# zasilanie.net
KiCad netlist of a schematic drawn in EAGLE
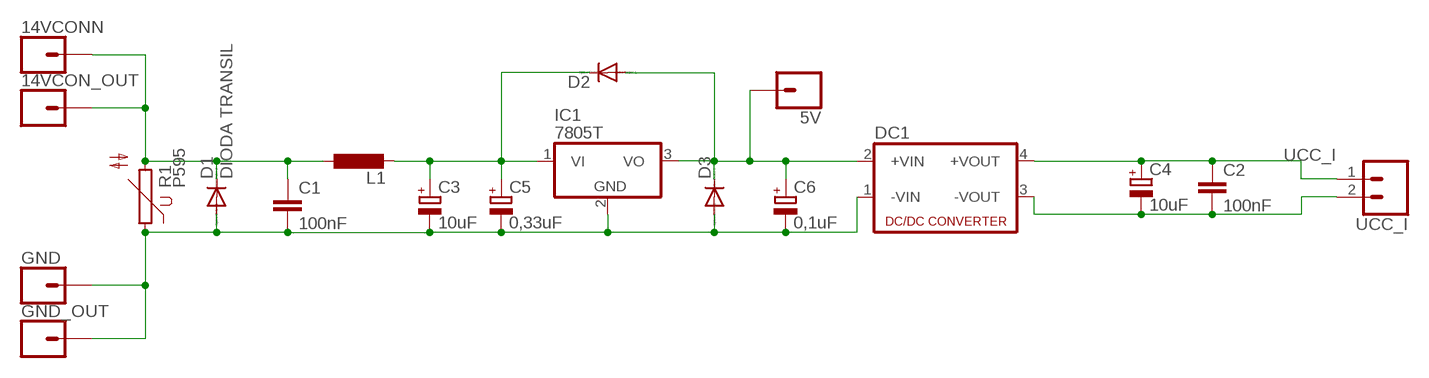
[diagram p0: schematic, sheet 1]

(export (version "E")
  (design (tool "Eeschema 10.0.6"))
  (components
    (comp (ref "5V")
      (value "CONN_01PTH_LONGPAD")
      (footprint "eagle-import:1X01_LONGPAD")
      (libsource (lib "eagle-import") (part "CONN_01PTH_LONGPAD"))
    )
    (comp (ref "14VCONN")
      (value "CONN_01PTH_LONGPAD")
      (footprint "eagle-import:1X01_LONGPAD")
      (libsource (lib "eagle-import") (part "CONN_01PTH_LONGPAD"))
    )
    (comp (ref "14VCON_OUT")
      (value "CONN_01PTH_LONGPAD")
      (footprint "eagle-import:1X01_LONGPAD")
      (libsource (lib "eagle-import") (part "CONN_01PTH_LONGPAD"))
    )
    (comp (ref "C1")
      (value "100nF")
      (footprint "eagle-import:C025-024X044")
      (libsource (lib "eagle-import") (part "C-EU025-024X044"))
    )
    (comp (ref "C2")
      (value "100nF")
      (footprint "eagle-import:C025-024X044")
      (libsource (lib "eagle-import") (part "C-EU025-024X044"))
    )
    (comp (ref "C3")
      (value "10uF")
      (footprint "eagle-import:E2,5-7")
      (libsource (lib "eagle-import") (part "CPOL-EUE2.5-7"))
    )
    (comp (ref "C4")
      (value "10uF")
      (footprint "eagle-import:E2,5-7")
      (libsource (lib "eagle-import") (part "CPOL-EUE2.5-7"))
    )
    (comp (ref "C5")
      (value "0,33uF")
      (footprint "eagle-import:E2,5-7")
      (libsource (lib "eagle-import") (part "CPOL-EUE2.5-7"))
    )
    (comp (ref "C6")
      (value "0,1uF")
      (footprint "eagle-import:E2,5-7")
      (libsource (lib "eagle-import") (part "CPOL-EUE2.5-7"))
    )
    (comp (ref "D1")
      (value "DIODA TRANSIL")
      (footprint "eagle-import:DO41-10")
      (libsource (lib "eagle-import") (part "1N4004"))
    )
    (comp (ref "D2")
      (value "1N4004")
      (footprint "eagle-import:DO41-10")
      (libsource (lib "eagle-import") (part "1N4004"))
    )
    (comp (ref "D3")
      (value "1N4004")
      (footprint "eagle-import:DO41-10")
      (libsource (lib "eagle-import") (part "1N4004"))
    )
    (comp (ref "DC1")
      (value "NME")
      (footprint "eagle-import:NME")
      (fields (field (name "MF") "C & D TECHNOLOGIES, INC") (field (name "MPN") "NME1205D"))
      (libsource (lib "eagle-import") (part "NME"))
    )
    (comp (ref "GND")
      (value "CONN_01PTH_LONGPAD")
      (footprint "eagle-import:1X01_LONGPAD")
      (libsource (lib "eagle-import") (part "CONN_01PTH_LONGPAD"))
    )
    (comp (ref "GND_OUT")
      (value "CONN_01PTH_LONGPAD")
      (footprint "eagle-import:1X01_LONGPAD")
      (libsource (lib "eagle-import") (part "CONN_01PTH_LONGPAD"))
    )
    (comp (ref "IC1")
      (value "7805T")
      (footprint "eagle-import:TO220H")
      (libsource (lib "eagle-import") (part "78T05"))
    )
    (comp (ref "L1")
      (value "L-EUTJ6-U1")
      (footprint "eagle-import:TJ6-U1")
      (libsource (lib "eagle-import") (part "L-EUTJ6-U1"))
    )
    (comp (ref "R1")
      (value "P595")
      (footprint "eagle-import:P595")
      (libsource (lib "eagle-import") (part "P595"))
    )
    (comp (ref "UCC_I")
      (value "CONN_02LOCK")
      (footprint "eagle-import:1X02_LOCK")
      (libsource (lib "eagle-import") (part "CONN_02LOCK"))
    )
  )
  (nets
    (net (code "1") (name "/UCC_I") (class "Default")
      (node (ref "C2") (pin "1") (pinfunction "1_1") (pintype "passive"))
      (node (ref "C4") (pin "+") (pinfunction "+_+") (pintype "passive"))
      (node (ref "DC1") (pin "4") (pinfunction "+VOUT_4") (pintype "passive"))
      (node (ref "UCC_I") (pin "1") (pinfunction "1_1") (pintype "passive"))
    )
    (net (code "2") (name "Net-(14VCONN-Pad1)") (class "Default")
      (node (ref "14VCONN") (pin "1") (pinfunction "1_1") (pintype "passive"))
      (node (ref "14VCON_OUT") (pin "1") (pinfunction "1_1") (pintype "passive"))
      (node (ref "C1") (pin "1") (pinfunction "1_1") (pintype "passive"))
      (node (ref "D1") (pin "C") (pinfunction "C_C") (pintype "passive"))
      (node (ref "L1") (pin "1") (pinfunction "1_1") (pintype "passive"))
      (node (ref "R1") (pin "2") (pinfunction "2_2") (pintype "passive"))
    )
    (net (code "3") (name "Net-(DC1-+VIN)") (class "Default")
      (node (ref "5V") (pin "1") (pinfunction "1_1") (pintype "passive"))
      (node (ref "C6") (pin "+") (pinfunction "+_+") (pintype "passive"))
      (node (ref "D2") (pin "A") (pinfunction "A_A") (pintype "passive"))
      (node (ref "D3") (pin "C") (pinfunction "C_C") (pintype "passive"))
      (node (ref "DC1") (pin "2") (pinfunction "+VIN_2") (pintype "passive"))
      (node (ref "IC1") (pin "3") (pinfunction "VO_3") (pintype "passive"))
    )
    (net (code "4") (name "Net-(DC1--VIN)") (class "Default")
      (node (ref "C1") (pin "2") (pinfunction "2_2") (pintype "passive"))
      (node (ref "C3") (pin "-") (pinfunction "-_-") (pintype "passive"))
      (node (ref "C5") (pin "-") (pinfunction "-_-") (pintype "passive"))
      (node (ref "C6") (pin "-") (pinfunction "-_-") (pintype "passive"))
      (node (ref "D1") (pin "A") (pinfunction "A_A") (pintype "passive"))
      (node (ref "D3") (pin "A") (pinfunction "A_A") (pintype "passive"))
      (node (ref "DC1") (pin "1") (pinfunction "-VIN_1") (pintype "passive"))
      (node (ref "GND") (pin "1") (pinfunction "1_1") (pintype "passive"))
      (node (ref "GND_OUT") (pin "1") (pinfunction "1_1") (pintype "passive"))
      (node (ref "IC1") (pin "2") (pinfunction "GND_2") (pintype "passive"))
      (node (ref "R1") (pin "1") (pinfunction "1_1") (pintype "passive"))
    )
    (net (code "5") (name "Net-(DC1--VOUT)") (class "Default")
      (node (ref "C2") (pin "2") (pinfunction "2_2") (pintype "passive"))
      (node (ref "C4") (pin "-") (pinfunction "-_-") (pintype "passive"))
      (node (ref "DC1") (pin "3") (pinfunction "-VOUT_3") (pintype "passive"))
      (node (ref "UCC_I") (pin "2") (pinfunction "2_2") (pintype "passive"))
    )
    (net (code "6") (name "Net-(IC1-VI)") (class "Default")
      (node (ref "C3") (pin "+") (pinfunction "+_+") (pintype "passive"))
      (node (ref "C5") (pin "+") (pinfunction "+_+") (pintype "passive"))
      (node (ref "D2") (pin "C") (pinfunction "C_C") (pintype "passive"))
      (node (ref "IC1") (pin "1") (pinfunction "VI_1") (pintype "input"))
      (node (ref "L1") (pin "2") (pinfunction "2_2") (pintype "passive"))
    )
  )
)
